# Work_Height_Sensor_Base_v1p1.net
KiCad netlist of a schematic drawn in EAGLE
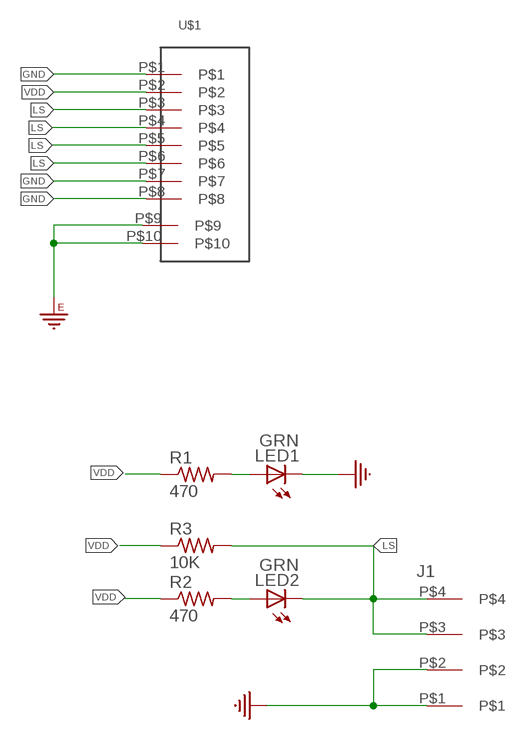
[diagram p0: schematic, sheet 1]

(export (version "E")
  (design (tool "Eeschema 10.0.6"))
  (components
    (comp (ref "J1")
      (value "3.81MM_1_X_4_RT_ANGLE_PLUG_HEADER")
      (footprint "eagle-import:1X4_3.81MM_PITCH")
      (libsource (lib "eagle-import") (part "3.81MM_1_X_4_RT_ANGLE_PLUG_HEADER"))
    )
    (comp (ref "LED1")
      (value "LED_0805_GREEN")
      (footprint "eagle-import:LED_0805_GREEN")
      (libsource (lib "eagle-import") (part "LED_0805_GREEN"))
    )
    (comp (ref "LED2")
      (value "LED_0805_GREEN")
      (footprint "eagle-import:LED_0805_GREEN")
      (libsource (lib "eagle-import") (part "LED_0805_GREEN"))
    )
    (comp (ref "R1")
      (value "470")
      (footprint "eagle-import:0402")
      (libsource (lib "eagle-import") (part "R_0402"))
    )
    (comp (ref "R2")
      (value "470")
      (footprint "eagle-import:0402")
      (libsource (lib "eagle-import") (part "R_0402"))
    )
    (comp (ref "R3")
      (value "10K")
      (footprint "eagle-import:0402")
      (libsource (lib "eagle-import") (part "R_0402"))
    )
    (comp (ref "U$1")
      (value "RJ45_SMTRJ")
      (footprint "eagle-import:RJ45_SMT")
      (libsource (lib "eagle-import") (part "RJ45_SMTRJ"))
    )
  )
  (nets
    (net (code "1") (name "GND") (class "Default")
      (node (ref "J1") (pin "P$1") (pinfunction "P$1_P$1") (pintype "bidirectional"))
      (node (ref "J1") (pin "P$2") (pinfunction "P$2_P$2") (pintype "bidirectional"))
      (node (ref "LED1") (pin "C") (pinfunction "C_C") (pintype "passive"))
      (node (ref "U$1") (pin "P$1") (pinfunction "P$1_P$1") (pintype "bidirectional"))
      (node (ref "U$1") (pin "P$7") (pinfunction "P$7_P$7") (pintype "bidirectional"))
      (node (ref "U$1") (pin "P$8") (pinfunction "P$8_P$8") (pintype "bidirectional"))
    )
    (net (code "2") (name "GNDEARTH") (class "Default")
      (node (ref "U$1") (pin "P$10") (pinfunction "P$10_P$10") (pintype "bidirectional"))
      (node (ref "U$1") (pin "P$9") (pinfunction "P$9_P$9") (pintype "bidirectional"))
    )
    (net (code "3") (name "LS") (class "Default")
      (node (ref "J1") (pin "P$3") (pinfunction "P$3_P$3") (pintype "bidirectional"))
      (node (ref "J1") (pin "P$4") (pinfunction "P$4_P$4") (pintype "bidirectional"))
      (node (ref "LED2") (pin "C") (pinfunction "C_C") (pintype "passive"))
      (node (ref "R3") (pin "P$2") (pinfunction "2_P$2") (pintype "passive"))
      (node (ref "U$1") (pin "P$3") (pinfunction "P$3_P$3") (pintype "bidirectional"))
      (node (ref "U$1") (pin "P$4") (pinfunction "P$4_P$4") (pintype "bidirectional"))
      (node (ref "U$1") (pin "P$5") (pinfunction "P$5_P$5") (pintype "bidirectional"))
      (node (ref "U$1") (pin "P$6") (pinfunction "P$6_P$6") (pintype "bidirectional"))
    )
    (net (code "4") (name "Net-(R1-2)") (class "Default")
      (node (ref "LED1") (pin "A") (pinfunction "A_A") (pintype "passive"))
      (node (ref "R1") (pin "P$2") (pinfunction "2_P$2") (pintype "passive"))
    )
    (net (code "5") (name "Net-(R2-2)") (class "Default")
      (node (ref "LED2") (pin "A") (pinfunction "A_A") (pintype "passive"))
      (node (ref "R2") (pin "P$2") (pinfunction "2_P$2") (pintype "passive"))
    )
    (net (code "6") (name "VDD") (class "Default")
      (node (ref "R1") (pin "P$1") (pinfunction "1_P$1") (pintype "passive"))
      (node (ref "R2") (pin "P$1") (pinfunction "1_P$1") (pintype "passive"))
      (node (ref "R3") (pin "P$1") (pinfunction "1_P$1") (pintype "passive"))
      (node (ref "U$1") (pin "P$2") (pinfunction "P$2_P$2") (pintype "bidirectional"))
    )
  )
)
